# Schematic.net
KiCad netlist of a schematic drawn in EAGLE
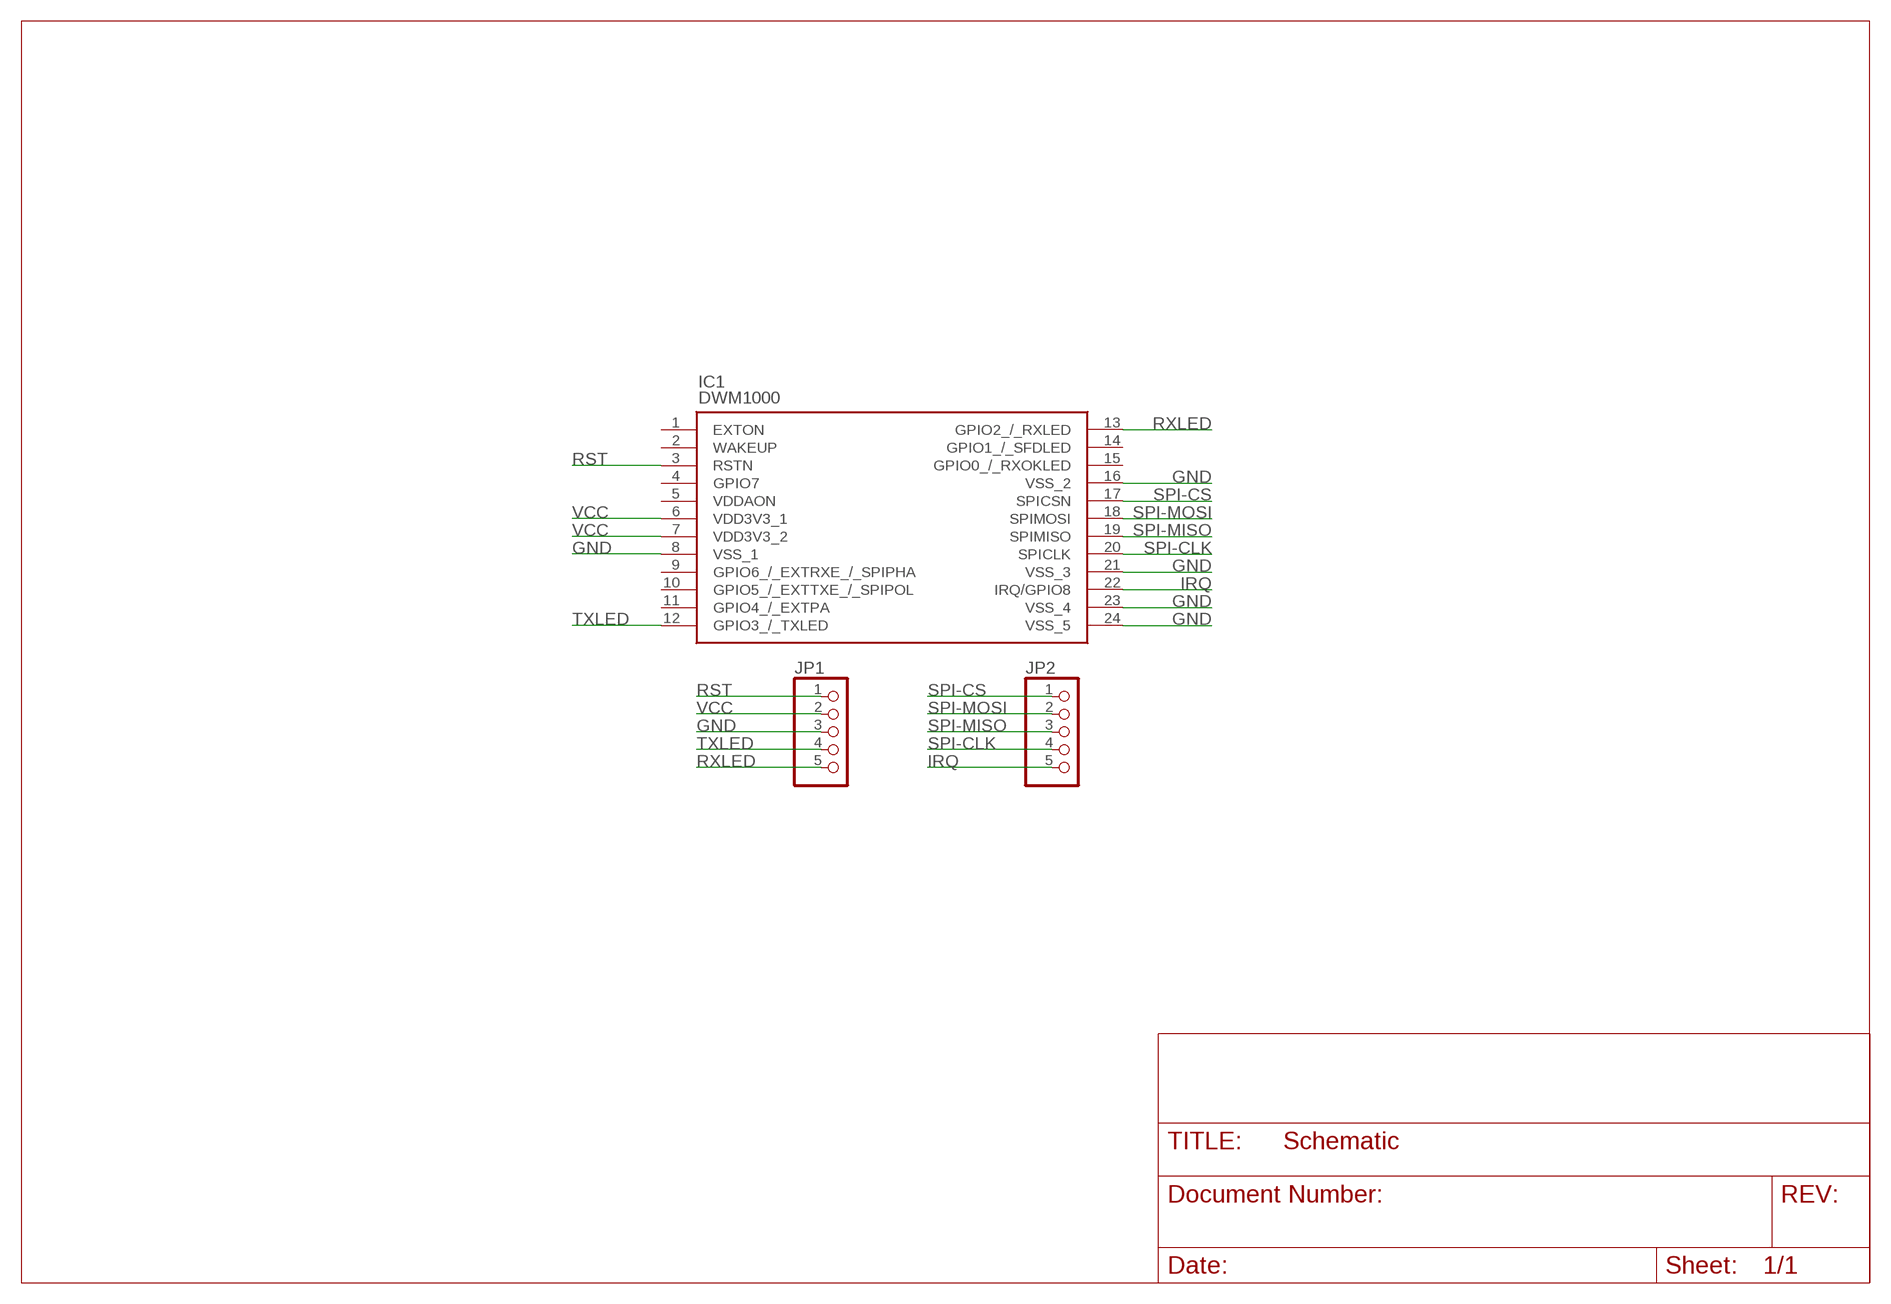
[diagram p0: schematic, sheet 1]

(export (version "E")
  (design (tool "Eeschema 10.0.6"))
  (components
    (comp (ref "IC1")
      (value "DWM1000")
      (footprint "eagle-import:DWM1000")
      (libsource (lib "eagle-import") (part "DWM1000"))
    )
    (comp (ref "JP1")
      (value "PINHD-1X5")
      (footprint "eagle-import:1X05")
      (libsource (lib "eagle-import") (part "PINHD-1X5"))
    )
    (comp (ref "JP2")
      (value "PINHD-1X5")
      (footprint "eagle-import:1X05")
      (libsource (lib "eagle-import") (part "PINHD-1X5"))
    )
  )
  (nets
    (net (code "1") (name "/GND") (class "Default")
      (node (ref "IC1") (pin "16") (pinfunction "VSS_2_16") (pintype "bidirectional"))
      (node (ref "IC1") (pin "21") (pinfunction "VSS_3_21") (pintype "bidirectional"))
      (node (ref "IC1") (pin "23") (pinfunction "VSS_4_23") (pintype "bidirectional"))
      (node (ref "IC1") (pin "24") (pinfunction "VSS_5_24") (pintype "bidirectional"))
      (node (ref "IC1") (pin "8") (pinfunction "VSS_1_8") (pintype "bidirectional"))
      (node (ref "JP1") (pin "3") (pinfunction "3_3") (pintype "passive"))
    )
    (net (code "2") (name "/IRQ") (class "Default")
      (node (ref "IC1") (pin "22") (pinfunction "IRQ/GPIO8_22") (pintype "bidirectional"))
      (node (ref "JP2") (pin "5") (pinfunction "5_5") (pintype "passive"))
    )
    (net (code "3") (name "/RST") (class "Default")
      (node (ref "IC1") (pin "3") (pinfunction "RSTN_3") (pintype "bidirectional"))
      (node (ref "JP1") (pin "1") (pinfunction "1_1") (pintype "passive"))
    )
    (net (code "4") (name "/RXLED") (class "Default")
      (node (ref "IC1") (pin "13") (pinfunction "GPIO2_/_RXLED_13") (pintype "bidirectional"))
      (node (ref "JP1") (pin "5") (pinfunction "5_5") (pintype "passive"))
    )
    (net (code "5") (name "/SPI-CLK") (class "Default")
      (node (ref "IC1") (pin "20") (pinfunction "SPICLK_20") (pintype "bidirectional"))
      (node (ref "JP2") (pin "4") (pinfunction "4_4") (pintype "passive"))
    )
    (net (code "6") (name "/SPI-CS") (class "Default")
      (node (ref "IC1") (pin "17") (pinfunction "SPICSN_17") (pintype "bidirectional"))
      (node (ref "JP2") (pin "1") (pinfunction "1_1") (pintype "passive"))
    )
    (net (code "7") (name "/SPI-MISO") (class "Default")
      (node (ref "IC1") (pin "19") (pinfunction "SPIMISO_19") (pintype "bidirectional"))
      (node (ref "JP2") (pin "3") (pinfunction "3_3") (pintype "passive"))
    )
    (net (code "8") (name "/SPI-MOSI") (class "Default")
      (node (ref "IC1") (pin "18") (pinfunction "SPIMOSI_18") (pintype "bidirectional"))
      (node (ref "JP2") (pin "2") (pinfunction "2_2") (pintype "passive"))
    )
    (net (code "9") (name "/TXLED") (class "Default")
      (node (ref "IC1") (pin "12") (pinfunction "GPIO3_/_TXLED_12") (pintype "bidirectional"))
      (node (ref "JP1") (pin "4") (pinfunction "4_4") (pintype "passive"))
    )
    (net (code "10") (name "/VCC") (class "Default")
      (node (ref "IC1") (pin "6") (pinfunction "VDD3V3_1_6") (pintype "bidirectional"))
      (node (ref "IC1") (pin "7") (pinfunction "VDD3V3_2_7") (pintype "bidirectional"))
      (node (ref "JP1") (pin "2") (pinfunction "2_2") (pintype "passive"))
    )
    (net (code "11") (name "unconnected-(IC1-EXTON-Pad1)") (class "Default")
      (node (ref "IC1") (pin "1") (pinfunction "EXTON_1") (pintype "bidirectional"))
    )
    (net (code "12") (name "unconnected-(IC1-GPIO0_{slash}_RXOKLED-Pad15)") (class "Default")
      (node (ref "IC1") (pin "15") (pinfunction "GPIO0_/_RXOKLED_15") (pintype "bidirectional"))
    )
    (net (code "13") (name "unconnected-(IC1-GPIO1_{slash}_SFDLED-Pad14)") (class "Default")
      (node (ref "IC1") (pin "14") (pinfunction "GPIO1_/_SFDLED_14") (pintype "bidirectional"))
    )
    (net (code "14") (name "unconnected-(IC1-GPIO4_{slash}_EXTPA-Pad11)") (class "Default")
      (node (ref "IC1") (pin "11") (pinfunction "GPIO4_/_EXTPA_11") (pintype "bidirectional"))
    )
    (net (code "15") (name "unconnected-(IC1-GPIO5_{slash}_EXTTXE_{slash}_SPIPOL-Pad10)") (class "Default")
      (node (ref "IC1") (pin "10") (pinfunction "GPIO5_/_EXTTXE_/_SPIPOL_10") (pintype "bidirectional"))
    )
    (net (code "16") (name "unconnected-(IC1-GPIO6_{slash}_EXTRXE_{slash}_SPIPHA-Pad9)") (class "Default")
      (node (ref "IC1") (pin "9") (pinfunction "GPIO6_/_EXTRXE_/_SPIPHA_9") (pintype "bidirectional"))
    )
    (net (code "17") (name "unconnected-(IC1-GPIO7-Pad4)") (class "Default")
      (node (ref "IC1") (pin "4") (pinfunction "GPIO7_4") (pintype "bidirectional"))
    )
    (net (code "18") (name "unconnected-(IC1-VDDAON-Pad5)") (class "Default")
      (node (ref "IC1") (pin "5") (pinfunction "VDDAON_5") (pintype "bidirectional"))
    )
    (net (code "19") (name "unconnected-(IC1-WAKEUP-Pad2)") (class "Default")
      (node (ref "IC1") (pin "2") (pinfunction "WAKEUP_2") (pintype "bidirectional"))
    )
  )
)
